# Sensors.net
KiCad netlist of a schematic drawn in Altium Designer
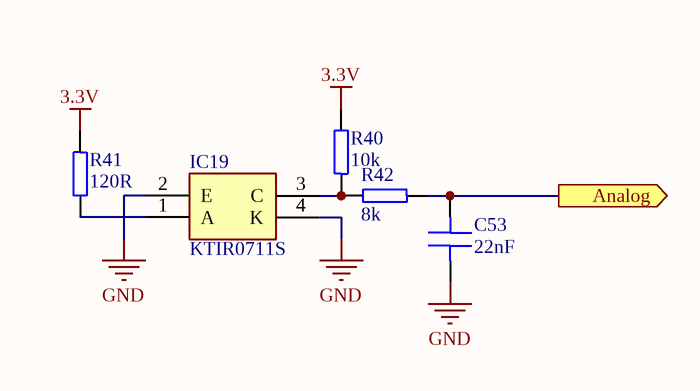
[diagram p0: Sensors.SchDoc]

(export (version "E")
  (design (tool "Eeschema 10.0.6"))
  (components
    (comp (ref "C53")
      (value "22nF")
      (footprint "C 0402")
      (description "MLCC Capacitor")
      (libsource (lib "Components") (part "Capacitor"))
    )
    (comp (ref "IC19")
      (value "KTIR0711S")
      (footprint "KTIR0711S")
      (description "Integrated Circuit")
      (libsource (lib "Library Loader") (part "KTIR0711S"))
    )
    (comp (ref "R40")
      (value "10k")
      (footprint "R 0402")
      (description "General pourpouse resistor")
      (libsource (lib "Components") (part "Resistor"))
    )
    (comp (ref "R41")
      (value "120R")
      (footprint "R 0402")
      (description "General pourpouse resistor")
      (libsource (lib "Components") (part "Resistor"))
    )
    (comp (ref "R42")
      (value "8k")
      (footprint "R 0402")
      (description "General pourpouse resistor")
      (libsource (lib "Components") (part "Resistor"))
    )
  )
  (nets
    (net (code "1") (name "/Analog") (class "Default")
      (node (ref "C53") (pin "1") (pinfunction "1_1") (pintype "passive"))
      (node (ref "R42") (pin "1") (pinfunction "1_1") (pintype "passive"))
    )
    (net (code "2") (name "3.3V") (class "Default")
      (node (ref "R40") (pin "2") (pinfunction "2_2") (pintype "passive"))
      (node (ref "R41") (pin "1") (pinfunction "1_1") (pintype "passive"))
    )
    (net (code "3") (name "GND") (class "Default")
      (node (ref "C53") (pin "2") (pinfunction "2_2") (pintype "passive"))
      (node (ref "IC19") (pin "2") (pinfunction "E_2") (pintype "passive"))
      (node (ref "IC19") (pin "4") (pinfunction "K_4") (pintype "passive"))
    )
    (net (code "4") (name "Net-(IC19-A)") (class "Default")
      (node (ref "IC19") (pin "1") (pinfunction "A_1") (pintype "passive"))
      (node (ref "R41") (pin "2") (pinfunction "2_2") (pintype "passive"))
    )
    (net (code "5") (name "Net-(IC19-C)") (class "Default")
      (node (ref "IC19") (pin "3") (pinfunction "C_3") (pintype "passive"))
      (node (ref "R40") (pin "1") (pinfunction "1_1") (pintype "passive"))
      (node (ref "R42") (pin "2") (pinfunction "2_2") (pintype "passive"))
    )
  )
)
